# Nixie_Tubes.net
KiCad netlist of a schematic drawn in Altium Designer
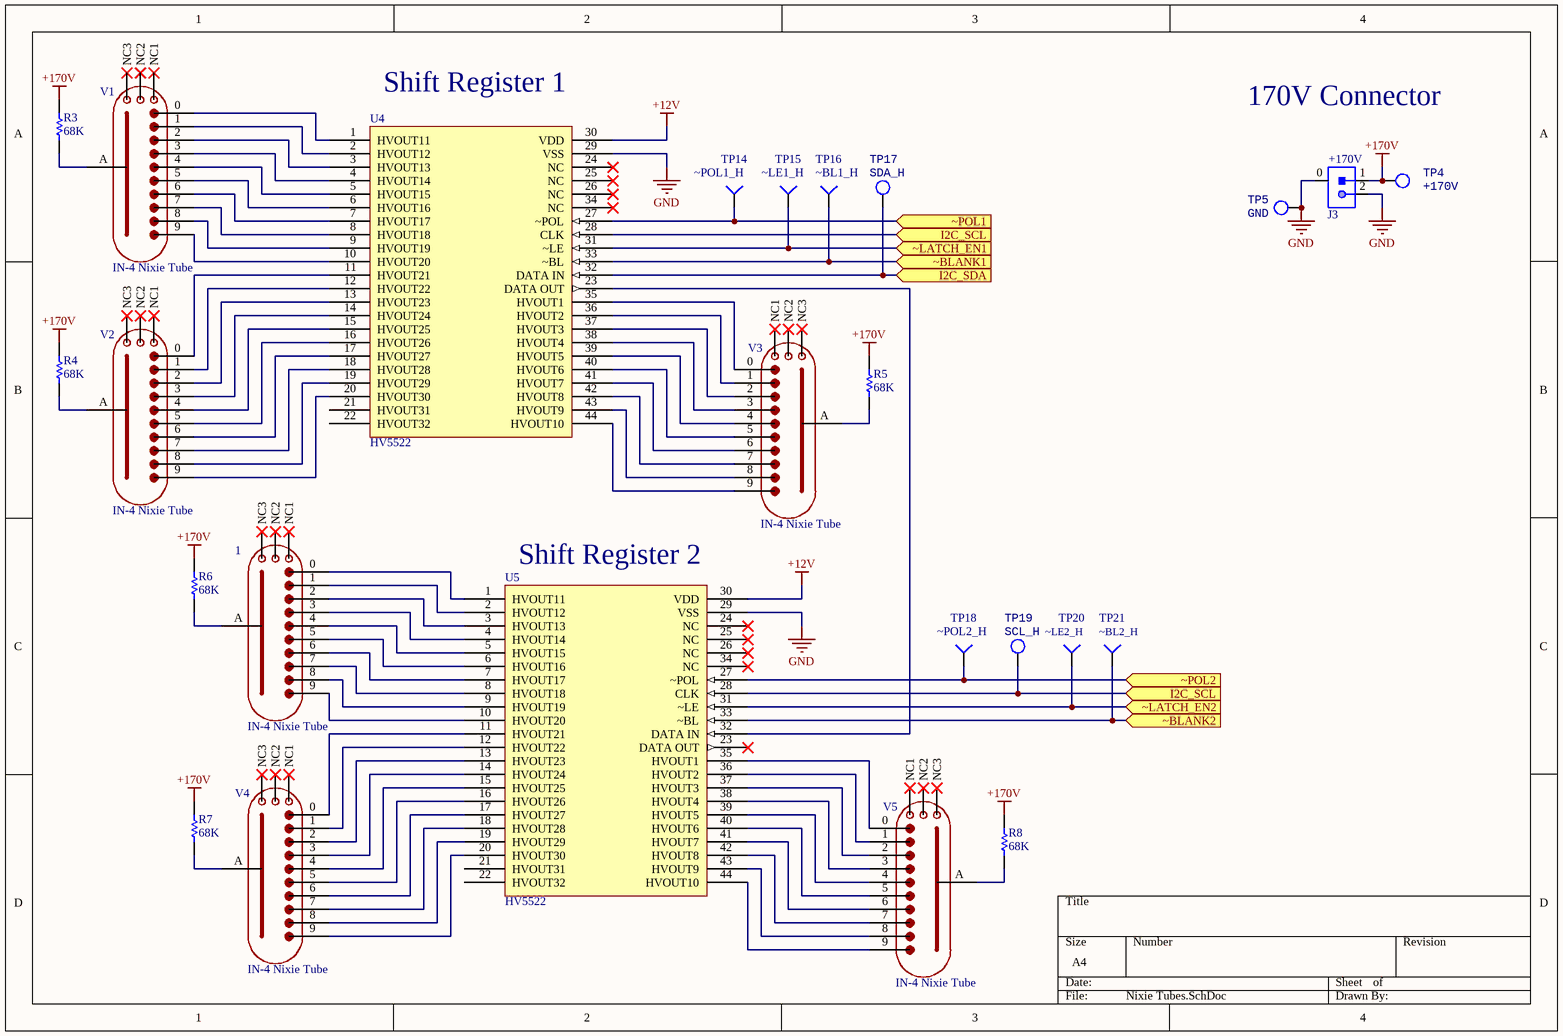
[diagram p0: Nixie Tubes.SchDoc]

(export (version "E")
  (design (tool "Eeschema 10.0.6"))
  (components
    (comp (ref "1") (value "IN-4 Nixie Tube") (libsource (lib "") (part "IN-4 Nixie Tube_1")))
    (comp (ref "J3")
      (value "+170V")
      (footprint "MOLEX-5024940270")
      (description "CONN HEADER SMD RIGHT ANGLE 2MM PITCH")
      (libsource (lib "Schlib_Nixie") (part "CON_2M_SM_RA"))
    )
    (comp (ref "R3")
      (value "68K")
      (footprint "RESC3225X60N")
      (description "RES SMD 68K OHM 1% 0.75W 1210")
      (fields (field (name "TOLERANCE") "1%") (field (name "Comment") "RES_68K_1210"))
      (libsource (lib "Schlib_Nixie") (part "RES_68K_1210"))
    )
    (comp (ref "R4")
      (value "68K")
      (footprint "RESC3225X60N")
      (description "RES SMD 68K OHM 1% 0.75W 1210")
      (fields (field (name "TOLERANCE") "1%") (field (name "Comment") "RES_68K_1210"))
      (libsource (lib "Schlib_Nixie") (part "RES_68K_1210"))
    )
    (comp (ref "R5")
      (value "68K")
      (footprint "RESC3225X60N")
      (description "RES SMD 68K OHM 1% 0.75W 1210")
      (fields (field (name "TOLERANCE") "1%") (field (name "Comment") "RES_68K_1210"))
      (libsource (lib "Schlib_Nixie") (part "RES_68K_1210"))
    )
    (comp (ref "R6")
      (value "68K")
      (footprint "RESC3225X60N")
      (description "RES SMD 68K OHM 1% 0.75W 1210")
      (fields (field (name "TOLERANCE") "1%") (field (name "Comment") "RES_68K_1210"))
      (libsource (lib "Schlib_Nixie") (part "RES_68K_1210"))
    )
    (comp (ref "R7")
      (value "68K")
      (footprint "RESC3225X60N")
      (description "RES SMD 68K OHM 1% 0.75W 1210")
      (fields (field (name "TOLERANCE") "1%") (field (name "Comment") "RES_68K_1210"))
      (libsource (lib "Schlib_Nixie") (part "RES_68K_1210"))
    )
    (comp (ref "R8")
      (value "68K")
      (footprint "RESC3225X60N")
      (description "RES SMD 68K OHM 1% 0.75W 1210")
      (fields (field (name "TOLERANCE") "1%") (field (name "Comment") "RES_68K_1210"))
      (libsource (lib "Schlib_Nixie") (part "RES_68K_1210"))
    )
    (comp (ref "TP4")
      (value "+170V")
      (footprint "TESTPOINT_LOOP")
      (description "Loop testpoint through-hole pad")
      (libsource (lib "Schlib_Nixie") (part "TESTPOINT_LOOP"))
    )
    (comp (ref "TP5")
      (value "GND")
      (footprint "TESTPOINT_LOOP")
      (description "Loop testpoint through-hole pad")
      (libsource (lib "Schlib_Nixie") (part "TESTPOINT_LOOP"))
    )
    (comp (ref "TP14")
      (value "~POL1_H")
      (footprint "TESTPOINT")
      (description "TESTPOINT_SMD")
      (libsource (lib "Schlib_Nixie") (part "TESTPOINT_SMD"))
    )
    (comp (ref "TP15")
      (value "~LE1_H")
      (footprint "TESTPOINT")
      (description "TESTPOINT_SMD")
      (libsource (lib "Schlib_Nixie") (part "TESTPOINT_SMD"))
    )
    (comp (ref "TP16")
      (value "~BL1_H")
      (footprint "TESTPOINT")
      (description "TESTPOINT_SMD")
      (libsource (lib "Schlib_Nixie") (part "TESTPOINT_SMD"))
    )
    (comp (ref "TP17")
      (value "SDA_H")
      (footprint "TESTPOINT_LOOP")
      (description "Loop testpoint through-hole pad")
      (libsource (lib "Schlib_Nixie") (part "TESTPOINT_LOOP"))
    )
    (comp (ref "TP18")
      (value "~POL2_H")
      (footprint "TESTPOINT")
      (description "TESTPOINT_SMD")
      (libsource (lib "Schlib_Nixie") (part "TESTPOINT_SMD"))
    )
    (comp (ref "TP19")
      (value "SCL_H")
      (footprint "TESTPOINT_LOOP")
      (description "Loop testpoint through-hole pad")
      (libsource (lib "Schlib_Nixie") (part "TESTPOINT_LOOP"))
    )
    (comp (ref "TP20")
      (value "~LE2_H")
      (footprint "TESTPOINT")
      (description "TESTPOINT_SMD")
      (libsource (lib "Schlib_Nixie") (part "TESTPOINT_SMD"))
    )
    (comp (ref "TP21")
      (value "~BL2_H")
      (footprint "TESTPOINT")
      (description "TESTPOINT_SMD")
      (libsource (lib "Schlib_Nixie") (part "TESTPOINT_SMD"))
    )
    (comp (ref "U4")
      (value "HV5522")
      (footprint "*QFP80P1320X1320X270-44N")
      (description "IC 32BIT SRL CMOS 220V 44QFP; Shift Shift Register 1 Element 32 Bit 44-PQFP (10x10)")
      (libsource (lib "Schlib_Nixie") (part "HV5522"))
    )
    (comp (ref "U5")
      (value "HV5522")
      (footprint "*QFP80P1320X1320X270-44N")
      (description "IC 32BIT SRL CMOS 220V 44QFP; Shift Shift Register 1 Element 32 Bit 44-PQFP (10x10)")
      (libsource (lib "Schlib_Nixie") (part "HV5522"))
    )
    (comp (ref "V1")
      (value "IN-4 Nixie Tube")
      (footprint "IN-4")
      (libsource (lib "") (part "IN-4 Nixie Tube_1"))
    )
    (comp (ref "V2") (value "IN-4 Nixie Tube") (libsource (lib "") (part "IN-4 Nixie Tube_1")))
    (comp (ref "V3") (value "IN-4 Nixie Tube") (libsource (lib "Schlib_Nixie") (part "IN-4 Nixie Tube")))
    (comp (ref "V4") (value "IN-4 Nixie Tube") (libsource (lib "") (part "IN-4 Nixie Tube_1")))
    (comp (ref "V5") (value "IN-4 Nixie Tube") (libsource (lib "Schlib_Nixie") (part "IN-4 Nixie Tube")))
  )
  (nets
    (net (code "1") (name "+12V") (class "Default")
      (node (ref "U4") (pin "30") (pinfunction "VDD_30") (pintype "power_in"))
      (node (ref "U5") (pin "30") (pinfunction "VDD_30") (pintype "power_in"))
    )
    (net (code "2") (name "+170V") (class "Default")
      (node (ref "J3") (pin "1") (pinfunction "1_1") (pintype "passive"))
      (node (ref "R3") (pin "2") (pinfunction "2_2") (pintype "passive"))
      (node (ref "R4") (pin "2") (pinfunction "2_2") (pintype "passive"))
      (node (ref "R5") (pin "2") (pinfunction "2_2") (pintype "passive"))
      (node (ref "R6") (pin "2") (pinfunction "2_2") (pintype "passive"))
      (node (ref "R7") (pin "2") (pinfunction "2_2") (pintype "passive"))
      (node (ref "R8") (pin "2") (pinfunction "2_2") (pintype "passive"))
      (node (ref "TP4") (pin "1") (pintype "passive"))
    )
    (net (code "3") (name "/I2C_SCL") (class "Default")
      (node (ref "TP19") (pin "1") (pintype "passive"))
      (node (ref "U4") (pin "28") (pinfunction "CLK_28") (pintype "input"))
      (node (ref "U5") (pin "28") (pinfunction "CLK_28") (pintype "input"))
    )
    (net (code "4") (name "/I2C_SDA") (class "Default")
      (node (ref "TP17") (pin "1") (pintype "passive"))
      (node (ref "U4") (pin "32") (pinfunction "DATA_IN_32") (pintype "input"))
    )
    (net (code "5") (name "/~BLANK1") (class "Default")
      (node (ref "TP16") (pin "1") (pinfunction "=value_1") (pintype "passive"))
      (node (ref "U4") (pin "33") (pinfunction "~BL_33") (pintype "input"))
    )
    (net (code "6") (name "/~BLANK2") (class "Default")
      (node (ref "TP21") (pin "1") (pinfunction "=value_1") (pintype "passive"))
      (node (ref "U5") (pin "33") (pinfunction "~BL_33") (pintype "input"))
    )
    (net (code "7") (name "/~LATCH_EN1") (class "Default")
      (node (ref "TP15") (pin "1") (pinfunction "=value_1") (pintype "passive"))
      (node (ref "U4") (pin "31") (pinfunction "~LE_31") (pintype "input"))
    )
    (net (code "8") (name "/~LATCH_EN2") (class "Default")
      (node (ref "TP20") (pin "1") (pinfunction "=value_1") (pintype "passive"))
      (node (ref "U5") (pin "31") (pinfunction "~LE_31") (pintype "input"))
    )
    (net (code "9") (name "/~POL1") (class "Default")
      (node (ref "TP14") (pin "1") (pinfunction "=value_1") (pintype "passive"))
      (node (ref "U4") (pin "27") (pinfunction "~POL_27") (pintype "input"))
    )
    (net (code "10") (name "/~POL2") (class "Default")
      (node (ref "TP18") (pin "1") (pinfunction "=value_1") (pintype "passive"))
      (node (ref "U5") (pin "27") (pinfunction "~POL_27") (pintype "input"))
    )
    (net (code "11") (name "GND") (class "Default")
      (node (ref "J3") (pin "0") (pinfunction "0_0") (pintype "passive"))
      (node (ref "J3") (pin "2") (pinfunction "2_2") (pintype "passive"))
      (node (ref "TP5") (pin "1") (pintype "passive"))
      (node (ref "U4") (pin "29") (pinfunction "VSS_29") (pintype "passive"))
      (node (ref "U5") (pin "29") (pinfunction "VSS_29") (pintype "passive"))
    )
    (net (code "12") (name "Net-(U4-DATA_OUT)") (class "Default")
      (node (ref "U4") (pin "23") (pinfunction "DATA_OUT_23") (pintype "output"))
      (node (ref "U5") (pin "32") (pinfunction "DATA_IN_32") (pintype "input"))
    )
    (net (code "13") (name "unconnected-(1-NC1-Pad10)") (class "Default")
      (node (ref "1") (pin "10") (pinfunction "NC1_10") (pintype "passive"))
    )
    (net (code "14") (name "unconnected-(1-NC2-Pad11)") (class "Default")
      (node (ref "1") (pin "11") (pinfunction "NC2_11") (pintype "passive"))
    )
    (net (code "15") (name "unconnected-(1-NC3-Pad12)") (class "Default")
      (node (ref "1") (pin "12") (pinfunction "NC3_12") (pintype "passive"))
    )
    (net (code "16") (name "unconnected-(1-P8-Pad0)") (class "Default")
      (node (ref "1") (pin "0") (pinfunction "P8_0") (pintype "passive"))
    )
    (net (code "17") (name "unconnected-(1-Pad1)") (class "Default")
      (node (ref "1") (pin "1") (pintype "passive"))
    )
    (net (code "18") (name "unconnected-(1-Pad2)") (class "Default")
      (node (ref "1") (pin "2") (pintype "passive"))
    )
    (net (code "19") (name "unconnected-(1-Pad3)") (class "Default")
      (node (ref "1") (pin "3") (pintype "passive"))
    )
    (net (code "20") (name "unconnected-(1-Pad4)") (class "Default")
      (node (ref "1") (pin "4") (pintype "passive"))
    )
    (net (code "21") (name "unconnected-(1-Pad5)") (class "Default")
      (node (ref "1") (pin "5") (pintype "passive"))
    )
    (net (code "22") (name "unconnected-(1-Pad6)") (class "Default")
      (node (ref "1") (pin "6") (pintype "passive"))
    )
    (net (code "23") (name "unconnected-(1-Pad7)") (class "Default")
      (node (ref "1") (pin "7") (pintype "passive"))
    )
    (net (code "24") (name "unconnected-(1-Pad8)") (class "Default")
      (node (ref "1") (pin "8") (pintype "passive"))
    )
    (net (code "25") (name "unconnected-(1-Pad9)") (class "Default")
      (node (ref "1") (pin "9") (pintype "passive"))
    )
    (net (code "26") (name "unconnected-(1-PadA)") (class "Default")
      (node (ref "1") (pin "A") (pintype "passive"))
    )
    (net (code "27") (name "unconnected-(R3-Pad1)") (class "Default")
      (node (ref "R3") (pin "1") (pinfunction "1_1") (pintype "passive"))
    )
    (net (code "28") (name "unconnected-(R4-Pad1)") (class "Default")
      (node (ref "R4") (pin "1") (pinfunction "1_1") (pintype "passive"))
    )
    (net (code "29") (name "unconnected-(R5-Pad1)") (class "Default")
      (node (ref "R5") (pin "1") (pinfunction "1_1") (pintype "passive"))
    )
    (net (code "30") (name "unconnected-(R6-Pad1)") (class "Default")
      (node (ref "R6") (pin "1") (pinfunction "1_1") (pintype "passive"))
    )
    (net (code "31") (name "unconnected-(R7-Pad1)") (class "Default")
      (node (ref "R7") (pin "1") (pinfunction "1_1") (pintype "passive"))
    )
    (net (code "32") (name "unconnected-(R8-Pad1)") (class "Default")
      (node (ref "R8") (pin "1") (pinfunction "1_1") (pintype "passive"))
    )
    (net (code "33") (name "unconnected-(U4-HVOUT1-Pad35)") (class "Default")
      (node (ref "U4") (pin "35") (pinfunction "HVOUT1_35") (pintype "passive"))
    )
    (net (code "34") (name "unconnected-(U4-HVOUT2-Pad36)") (class "Default")
      (node (ref "U4") (pin "36") (pinfunction "HVOUT2_36") (pintype "passive"))
    )
    (net (code "35") (name "unconnected-(U4-HVOUT3-Pad37)") (class "Default")
      (node (ref "U4") (pin "37") (pinfunction "HVOUT3_37") (pintype "passive"))
    )
    (net (code "36") (name "unconnected-(U4-HVOUT4-Pad38)") (class "Default")
      (node (ref "U4") (pin "38") (pinfunction "HVOUT4_38") (pintype "passive"))
    )
    (net (code "37") (name "unconnected-(U4-HVOUT5-Pad39)") (class "Default")
      (node (ref "U4") (pin "39") (pinfunction "HVOUT5_39") (pintype "passive"))
    )
    (net (code "38") (name "unconnected-(U4-HVOUT6-Pad40)") (class "Default")
      (node (ref "U4") (pin "40") (pinfunction "HVOUT6_40") (pintype "passive"))
    )
    (net (code "39") (name "unconnected-(U4-HVOUT7-Pad41)") (class "Default")
      (node (ref "U4") (pin "41") (pinfunction "HVOUT7_41") (pintype "passive"))
    )
    (net (code "40") (name "unconnected-(U4-HVOUT8-Pad42)") (class "Default")
      (node (ref "U4") (pin "42") (pinfunction "HVOUT8_42") (pintype "passive"))
    )
    (net (code "41") (name "unconnected-(U4-HVOUT9-Pad43)") (class "Default")
      (node (ref "U4") (pin "43") (pinfunction "HVOUT9_43") (pintype "passive"))
    )
    (net (code "42") (name "unconnected-(U4-HVOUT10-Pad44)") (class "Default")
      (node (ref "U4") (pin "44") (pinfunction "HVOUT10_44") (pintype "passive"))
    )
    (net (code "43") (name "unconnected-(U4-HVOUT11-Pad1)") (class "Default")
      (node (ref "U4") (pin "1") (pinfunction "HVOUT11_1") (pintype "open_collector"))
    )
    (net (code "44") (name "unconnected-(U4-HVOUT12-Pad2)") (class "Default")
      (node (ref "U4") (pin "2") (pinfunction "HVOUT12_2") (pintype "passive"))
    )
    (net (code "45") (name "unconnected-(U4-HVOUT13-Pad3)") (class "Default")
      (node (ref "U4") (pin "3") (pinfunction "HVOUT13_3") (pintype "passive"))
    )
    (net (code "46") (name "unconnected-(U4-HVOUT14-Pad4)") (class "Default")
      (node (ref "U4") (pin "4") (pinfunction "HVOUT14_4") (pintype "passive"))
    )
    (net (code "47") (name "unconnected-(U4-HVOUT15-Pad5)") (class "Default")
      (node (ref "U4") (pin "5") (pinfunction "HVOUT15_5") (pintype "passive"))
    )
    (net (code "48") (name "unconnected-(U4-HVOUT16-Pad6)") (class "Default")
      (node (ref "U4") (pin "6") (pinfunction "HVOUT16_6") (pintype "passive"))
    )
    (net (code "49") (name "unconnected-(U4-HVOUT17-Pad7)") (class "Default")
      (node (ref "U4") (pin "7") (pinfunction "HVOUT17_7") (pintype "passive"))
    )
    (net (code "50") (name "unconnected-(U4-HVOUT18-Pad8)") (class "Default")
      (node (ref "U4") (pin "8") (pinfunction "HVOUT18_8") (pintype "passive"))
    )
    (net (code "51") (name "unconnected-(U4-HVOUT19-Pad9)") (class "Default")
      (node (ref "U4") (pin "9") (pinfunction "HVOUT19_9") (pintype "passive"))
    )
    (net (code "52") (name "unconnected-(U4-HVOUT20-Pad10)") (class "Default")
      (node (ref "U4") (pin "10") (pinfunction "HVOUT20_10") (pintype "passive"))
    )
    (net (code "53") (name "unconnected-(U4-HVOUT21-Pad11)") (class "Default")
      (node (ref "U4") (pin "11") (pinfunction "HVOUT21_11") (pintype "passive"))
    )
    (net (code "54") (name "unconnected-(U4-HVOUT22-Pad12)") (class "Default")
      (node (ref "U4") (pin "12") (pinfunction "HVOUT22_12") (pintype "passive"))
    )
    (net (code "55") (name "unconnected-(U4-HVOUT23-Pad13)") (class "Default")
      (node (ref "U4") (pin "13") (pinfunction "HVOUT23_13") (pintype "passive"))
    )
    (net (code "56") (name "unconnected-(U4-HVOUT24-Pad14)") (class "Default")
      (node (ref "U4") (pin "14") (pinfunction "HVOUT24_14") (pintype "passive"))
    )
    (net (code "57") (name "unconnected-(U4-HVOUT25-Pad15)") (class "Default")
      (node (ref "U4") (pin "15") (pinfunction "HVOUT25_15") (pintype "passive"))
    )
    (net (code "58") (name "unconnected-(U4-HVOUT26-Pad16)") (class "Default")
      (node (ref "U4") (pin "16") (pinfunction "HVOUT26_16") (pintype "passive"))
    )
    (net (code "59") (name "unconnected-(U4-HVOUT27-Pad17)") (class "Default")
      (node (ref "U4") (pin "17") (pinfunction "HVOUT27_17") (pintype "passive"))
    )
    (net (code "60") (name "unconnected-(U4-HVOUT28-Pad18)") (class "Default")
      (node (ref "U4") (pin "18") (pinfunction "HVOUT28_18") (pintype "passive"))
    )
    (net (code "61") (name "unconnected-(U4-HVOUT29-Pad19)") (class "Default")
      (node (ref "U4") (pin "19") (pinfunction "HVOUT29_19") (pintype "passive"))
    )
    (net (code "62") (name "unconnected-(U4-HVOUT30-Pad20)") (class "Default")
      (node (ref "U4") (pin "20") (pinfunction "HVOUT30_20") (pintype "passive"))
    )
    (net (code "63") (name "unconnected-(U4-HVOUT31-Pad21)") (class "Default")
      (node (ref "U4") (pin "21") (pinfunction "HVOUT31_21") (pintype "passive"))
    )
    (net (code "64") (name "unconnected-(U4-HVOUT32-Pad22)") (class "Default")
      (node (ref "U4") (pin "22") (pinfunction "HVOUT32_22") (pintype "passive"))
    )
    (net (code "65") (name "unconnected-(U4-NC-Pad24)") (class "Default")
      (node (ref "U4") (pin "24") (pinfunction "NC_24") (pintype "passive+no_connect"))
    )
    (net (code "66") (name "unconnected-(U4-NC-Pad25)") (class "Default")
      (node (ref "U4") (pin "25") (pinfunction "NC_25") (pintype "passive+no_connect"))
    )
    (net (code "67") (name "unconnected-(U4-NC-Pad26)") (class "Default")
      (node (ref "U4") (pin "26") (pinfunction "NC_26") (pintype "passive+no_connect"))
    )
    (net (code "68") (name "unconnected-(U4-NC-Pad34)") (class "Default")
      (node (ref "U4") (pin "34") (pinfunction "NC_34") (pintype "passive+no_connect"))
    )
    (net (code "69") (name "unconnected-(U5-DATA_OUT-Pad23)") (class "Default")
      (node (ref "U5") (pin "23") (pinfunction "DATA_OUT_23") (pintype "output+no_connect"))
    )
    (net (code "70") (name "unconnected-(U5-HVOUT1-Pad35)") (class "Default")
      (node (ref "U5") (pin "35") (pinfunction "HVOUT1_35") (pintype "passive"))
    )
    (net (code "71") (name "unconnected-(U5-HVOUT2-Pad36)") (class "Default")
      (node (ref "U5") (pin "36") (pinfunction "HVOUT2_36") (pintype "passive"))
    )
    (net (code "72") (name "unconnected-(U5-HVOUT3-Pad37)") (class "Default")
      (node (ref "U5") (pin "37") (pinfunction "HVOUT3_37") (pintype "passive"))
    )
    (net (code "73") (name "unconnected-(U5-HVOUT4-Pad38)") (class "Default")
      (node (ref "U5") (pin "38") (pinfunction "HVOUT4_38") (pintype "passive"))
    )
    (net (code "74") (name "unconnected-(U5-HVOUT5-Pad39)") (class "Default")
      (node (ref "U5") (pin "39") (pinfunction "HVOUT5_39") (pintype "passive"))
    )
    (net (code "75") (name "unconnected-(U5-HVOUT6-Pad40)") (class "Default")
      (node (ref "U5") (pin "40") (pinfunction "HVOUT6_40") (pintype "passive"))
    )
    (net (code "76") (name "unconnected-(U5-HVOUT7-Pad41)") (class "Default")
      (node (ref "U5") (pin "41") (pinfunction "HVOUT7_41") (pintype "passive"))
    )
    (net (code "77") (name "unconnected-(U5-HVOUT8-Pad42)") (class "Default")
      (node (ref "U5") (pin "42") (pinfunction "HVOUT8_42") (pintype "passive"))
    )
    (net (code "78") (name "unconnected-(U5-HVOUT9-Pad43)") (class "Default")
      (node (ref "U5") (pin "43") (pinfunction "HVOUT9_43") (pintype "passive"))
    )
    (net (code "79") (name "unconnected-(U5-HVOUT10-Pad44)") (class "Default")
      (node (ref "U5") (pin "44") (pinfunction "HVOUT10_44") (pintype "passive"))
    )
    (net (code "80") (name "unconnected-(U5-HVOUT11-Pad1)") (class "Default")
      (node (ref "U5") (pin "1") (pinfunction "HVOUT11_1") (pintype "open_collector"))
    )
    (net (code "81") (name "unconnected-(U5-HVOUT12-Pad2)") (class "Default")
      (node (ref "U5") (pin "2") (pinfunction "HVOUT12_2") (pintype "passive"))
    )
    (net (code "82") (name "unconnected-(U5-HVOUT13-Pad3)") (class "Default")
      (node (ref "U5") (pin "3") (pinfunction "HVOUT13_3") (pintype "passive"))
    )
    (net (code "83") (name "unconnected-(U5-HVOUT14-Pad4)") (class "Default")
      (node (ref "U5") (pin "4") (pinfunction "HVOUT14_4") (pintype "passive"))
    )
    (net (code "84") (name "unconnected-(U5-HVOUT15-Pad5)") (class "Default")
      (node (ref "U5") (pin "5") (pinfunction "HVOUT15_5") (pintype "passive"))
    )
    (net (code "85") (name "unconnected-(U5-HVOUT16-Pad6)") (class "Default")
      (node (ref "U5") (pin "6") (pinfunction "HVOUT16_6") (pintype "passive"))
    )
    (net (code "86") (name "unconnected-(U5-HVOUT17-Pad7)") (class "Default")
      (node (ref "U5") (pin "7") (pinfunction "HVOUT17_7") (pintype "passive"))
    )
    (net (code "87") (name "unconnected-(U5-HVOUT18-Pad8)") (class "Default")
      (node (ref "U5") (pin "8") (pinfunction "HVOUT18_8") (pintype "passive"))
    )
    (net (code "88") (name "unconnected-(U5-HVOUT19-Pad9)") (class "Default")
      (node (ref "U5") (pin "9") (pinfunction "HVOUT19_9") (pintype "passive"))
    )
    (net (code "89") (name "unconnected-(U5-HVOUT20-Pad10)") (class "Default")
      (node (ref "U5") (pin "10") (pinfunction "HVOUT20_10") (pintype "passive"))
    )
    (net (code "90") (name "unconnected-(U5-HVOUT21-Pad11)") (class "Default")
      (node (ref "U5") (pin "11") (pinfunction "HVOUT21_11") (pintype "passive"))
    )
    (net (code "91") (name "unconnected-(U5-HVOUT22-Pad12)") (class "Default")
      (node (ref "U5") (pin "12") (pinfunction "HVOUT22_12") (pintype "passive"))
    )
    (net (code "92") (name "unconnected-(U5-HVOUT23-Pad13)") (class "Default")
      (node (ref "U5") (pin "13") (pinfunction "HVOUT23_13") (pintype "passive"))
    )
    (net (code "93") (name "unconnected-(U5-HVOUT24-Pad14)") (class "Default")
      (node (ref "U5") (pin "14") (pinfunction "HVOUT24_14") (pintype "passive"))
    )
    (net (code "94") (name "unconnected-(U5-HVOUT25-Pad15)") (class "Default")
      (node (ref "U5") (pin "15") (pinfunction "HVOUT25_15") (pintype "passive"))
    )
    (net (code "95") (name "unconnected-(U5-HVOUT26-Pad16)") (class "Default")
      (node (ref "U5") (pin "16") (pinfunction "HVOUT26_16") (pintype "passive"))
    )
    (net (code "96") (name "unconnected-(U5-HVOUT27-Pad17)") (class "Default")
      (node (ref "U5") (pin "17") (pinfunction "HVOUT27_17") (pintype "passive"))
    )
    (net (code "97") (name "unconnected-(U5-HVOUT28-Pad18)") (class "Default")
      (node (ref "U5") (pin "18") (pinfunction "HVOUT28_18") (pintype "passive"))
    )
    (net (code "98") (name "unconnected-(U5-HVOUT29-Pad19)") (class "Default")
      (node (ref "U5") (pin "19") (pinfunction "HVOUT29_19") (pintype "passive"))
    )
    (net (code "99") (name "unconnected-(U5-HVOUT30-Pad20)") (class "Default")
      (node (ref "U5") (pin "20") (pinfunction "HVOUT30_20") (pintype "passive"))
    )
    (net (code "100") (name "unconnected-(U5-HVOUT31-Pad21)") (class "Default")
      (node (ref "U5") (pin "21") (pinfunction "HVOUT31_21") (pintype "passive"))
    )
    (net (code "101") (name "unconnected-(U5-HVOUT32-Pad22)") (class "Default")
      (node (ref "U5") (pin "22") (pinfunction "HVOUT32_22") (pintype "passive"))
    )
    (net (code "102") (name "unconnected-(U5-NC-Pad24)") (class "Default")
      (node (ref "U5") (pin "24") (pinfunction "NC_24") (pintype "passive+no_connect"))
    )
    (net (code "103") (name "unconnected-(U5-NC-Pad25)") (class "Default")
      (node (ref "U5") (pin "25") (pinfunction "NC_25") (pintype "passive+no_connect"))
    )
    (net (code "104") (name "unconnected-(U5-NC-Pad26)") (class "Default")
      (node (ref "U5") (pin "26") (pinfunction "NC_26") (pintype "passive+no_connect"))
    )
    (net (code "105") (name "unconnected-(U5-NC-Pad34)") (class "Default")
      (node (ref "U5") (pin "34") (pinfunction "NC_34") (pintype "passive+no_connect"))
    )
    (net (code "106") (name "unconnected-(V1-NC1-Pad10)") (class "Default")
      (node (ref "V1") (pin "10") (pinfunction "NC1_10") (pintype "passive"))
    )
    (net (code "107") (name "unconnected-(V1-NC2-Pad11)") (class "Default")
      (node (ref "V1") (pin "11") (pinfunction "NC2_11") (pintype "passive"))
    )
    (net (code "108") (name "unconnected-(V1-NC3-Pad12)") (class "Default")
      (node (ref "V1") (pin "12") (pinfunction "NC3_12") (pintype "passive"))
    )
    (net (code "109") (name "unconnected-(V1-P8-Pad0)") (class "Default")
      (node (ref "V1") (pin "0") (pinfunction "P8_0") (pintype "passive"))
    )
    (net (code "110") (name "unconnected-(V1-Pad1)") (class "Default")
      (node (ref "V1") (pin "1") (pintype "passive"))
    )
    (net (code "111") (name "unconnected-(V1-Pad2)") (class "Default")
      (node (ref "V1") (pin "2") (pintype "passive"))
    )
    (net (code "112") (name "unconnected-(V1-Pad3)") (class "Default")
      (node (ref "V1") (pin "3") (pintype "passive"))
    )
    (net (code "113") (name "unconnected-(V1-Pad4)") (class "Default")
      (node (ref "V1") (pin "4") (pintype "passive"))
    )
    (net (code "114") (name "unconnected-(V1-Pad5)") (class "Default")
      (node (ref "V1") (pin "5") (pintype "passive"))
    )
    (net (code "115") (name "unconnected-(V1-Pad6)") (class "Default")
      (node (ref "V1") (pin "6") (pintype "passive"))
    )
    (net (code "116") (name "unconnected-(V1-Pad7)") (class "Default")
      (node (ref "V1") (pin "7") (pintype "passive"))
    )
    (net (code "117") (name "unconnected-(V1-Pad8)") (class "Default")
      (node (ref "V1") (pin "8") (pintype "passive"))
    )
    (net (code "118") (name "unconnected-(V1-Pad9)") (class "Default")
      (node (ref "V1") (pin "9") (pintype "passive"))
    )
    (net (code "119") (name "unconnected-(V1-PadA)") (class "Default")
      (node (ref "V1") (pin "A") (pintype "passive"))
    )
    (net (code "120") (name "unconnected-(V2-NC1-Pad10)") (class "Default")
      (node (ref "V2") (pin "10") (pinfunction "NC1_10") (pintype "passive"))
    )
    (net (code "121") (name "unconnected-(V2-NC2-Pad11)") (class "Default")
      (node (ref "V2") (pin "11") (pinfunction "NC2_11") (pintype "passive"))
    )
    (net (code "122") (name "unconnected-(V2-NC3-Pad12)") (class "Default")
      (node (ref "V2") (pin "12") (pinfunction "NC3_12") (pintype "passive"))
    )
    (net (code "123") (name "unconnected-(V2-P8-Pad0)") (class "Default")
      (node (ref "V2") (pin "0") (pinfunction "P8_0") (pintype "passive"))
    )
    (net (code "124") (name "unconnected-(V2-Pad1)") (class "Default")
      (node (ref "V2") (pin "1") (pintype "passive"))
    )
    (net (code "125") (name "unconnected-(V2-Pad2)") (class "Default")
      (node (ref "V2") (pin "2") (pintype "passive"))
    )
    (net (code "126") (name "unconnected-(V2-Pad3)") (class "Default")
      (node (ref "V2") (pin "3") (pintype "passive"))
    )
    (net (code "127") (name "unconnected-(V2-Pad4)") (class "Default")
      (node (ref "V2") (pin "4") (pintype "passive"))
    )
    (net (code "128") (name "unconnected-(V2-Pad5)") (class "Default")
      (node (ref "V2") (pin "5") (pintype "passive"))
    )
    (net (code "129") (name "unconnected-(V2-Pad6)") (class "Default")
      (node (ref "V2") (pin "6") (pintype "passive"))
    )
    (net (code "130") (name "unconnected-(V2-Pad7)") (class "Default")
      (node (ref "V2") (pin "7") (pintype "passive"))
    )
    (net (code "131") (name "unconnected-(V2-Pad8)") (class "Default")
      (node (ref "V2") (pin "8") (pintype "passive"))
    )
    (net (code "132") (name "unconnected-(V2-Pad9)") (class "Default")
      (node (ref "V2") (pin "9") (pintype "passive"))
    )
    (net (code "133") (name "unconnected-(V2-PadA)") (class "Default")
      (node (ref "V2") (pin "A") (pintype "passive"))
    )
    (net (code "134") (name "unconnected-(V3-NC1-Pad10)") (class "Default")
      (node (ref "V3") (pin "10") (pinfunction "NC1_10") (pintype "passive"))
    )
    (net (code "135") (name "unconnected-(V3-NC2-Pad11)") (class "Default")
      (node (ref "V3") (pin "11") (pinfunction "NC2_11") (pintype "passive"))
    )
    (net (code "136") (name "unconnected-(V3-NC3-Pad12)") (class "Default")
      (node (ref "V3") (pin "12") (pinfunction "NC3_12") (pintype "passive"))
    )
    (net (code "137") (name "unconnected-(V3-P8-Pad0)") (class "Default")
      (node (ref "V3") (pin "0") (pinfunction "P8_0") (pintype "passive"))
    )
    (net (code "138") (name "unconnected-(V3-Pad1)") (class "Default")
      (node (ref "V3") (pin "1") (pintype "passive"))
    )
    (net (code "139") (name "unconnected-(V3-Pad2)") (class "Default")
      (node (ref "V3") (pin "2") (pintype "passive"))
    )
    (net (code "140") (name "unconnected-(V3-Pad3)") (class "Default")
      (node (ref "V3") (pin "3") (pintype "passive"))
    )
    (net (code "141") (name "unconnected-(V3-Pad4)") (class "Default")
      (node (ref "V3") (pin "4") (pintype "passive"))
    )
    (net (code "142") (name "unconnected-(V3-Pad5)") (class "Default")
      (node (ref "V3") (pin "5") (pintype "passive"))
    )
    (net (code "143") (name "unconnected-(V3-Pad6)") (class "Default")
      (node (ref "V3") (pin "6") (pintype "passive"))
    )
    (net (code "144") (name "unconnected-(V3-Pad7)") (class "Default")
      (node (ref "V3") (pin "7") (pintype "passive"))
    )
    (net (code "145") (name "unconnected-(V3-Pad8)") (class "Default")
      (node (ref "V3") (pin "8") (pintype "passive"))
    )
    (net (code "146") (name "unconnected-(V3-Pad9)") (class "Default")
      (node (ref "V3") (pin "9") (pintype "passive"))
    )
    (net (code "147") (name "unconnected-(V3-PadA)") (class "Default")
      (node (ref "V3") (pin "A") (pintype "passive"))
    )
    (net (code "148") (name "unconnected-(V4-NC1-Pad10)") (class "Default")
      (node (ref "V4") (pin "10") (pinfunction "NC1_10") (pintype "passive"))
    )
    (net (code "149") (name "unconnected-(V4-NC2-Pad11)") (class "Default")
      (node (ref "V4") (pin "11") (pinfunction "NC2_11") (pintype "passive"))
    )
    (net (code "150") (name "unconnected-(V4-NC3-Pad12)") (class "Default")
      (node (ref "V4") (pin "12") (pinfunction "NC3_12") (pintype "passive"))
    )
    (net (code "151") (name "unconnected-(V4-P8-Pad0)") (class "Default")
      (node (ref "V4") (pin "0") (pinfunction "P8_0") (pintype "passive"))
    )
    (net (code "152") (name "unconnected-(V4-Pad1)") (class "Default")
      (node (ref "V4") (pin "1") (pintype "passive"))
    )
    (net (code "153") (name "unconnected-(V4-Pad2)") (class "Default")
      (node (ref "V4") (pin "2") (pintype "passive"))
    )
    (net (code "154") (name "unconnected-(V4-Pad3)") (class "Default")
      (node (ref "V4") (pin "3") (pintype "passive"))
    )
    (net (code "155") (name "unconnected-(V4-Pad4)") (class "Default")
      (node (ref "V4") (pin "4") (pintype "passive"))
    )
    (net (code "156") (name "unconnected-(V4-Pad5)") (class "Default")
      (node (ref "V4") (pin "5") (pintype "passive"))
    )
    (net (code "157") (name "unconnected-(V4-Pad6)") (class "Default")
      (node (ref "V4") (pin "6") (pintype "passive"))
    )
    (net (code "158") (name "unconnected-(V4-Pad7)") (class "Default")
      (node (ref "V4") (pin "7") (pintype "passive"))
    )
    (net (code "159") (name "unconnected-(V4-Pad8)") (class "Default")
      (node (ref "V4") (pin "8") (pintype "passive"))
    )
    (net (code "160") (name "unconnected-(V4-Pad9)") (class "Default")
      (node (ref "V4") (pin "9") (pintype "passive"))
    )
    (net (code "161") (name "unconnected-(V4-PadA)") (class "Default")
      (node (ref "V4") (pin "A") (pintype "passive"))
    )
    (net (code "162") (name "unconnected-(V5-NC1-Pad10)") (class "Default")
      (node (ref "V5") (pin "10") (pinfunction "NC1_10") (pintype "passive"))
    )
    (net (code "163") (name "unconnected-(V5-NC2-Pad11)") (class "Default")
      (node (ref "V5") (pin "11") (pinfunction "NC2_11") (pintype "passive"))
    )
    (net (code "164") (name "unconnected-(V5-NC3-Pad12)") (class "Default")
      (node (ref "V5") (pin "12") (pinfunction "NC3_12") (pintype "passive"))
    )
    (net (code "165") (name "unconnected-(V5-P8-Pad0)") (class "Default")
      (node (ref "V5") (pin "0") (pinfunction "P8_0") (pintype "passive"))
    )
    (net (code "166") (name "unconnected-(V5-Pad1)") (class "Default")
      (node (ref "V5") (pin "1") (pintype "passive"))
    )
    (net (code "167") (name "unconnected-(V5-Pad2)") (class "Default")
      (node (ref "V5") (pin "2") (pintype "passive"))
    )
    (net (code "168") (name "unconnected-(V5-Pad3)") (class "Default")
      (node (ref "V5") (pin "3") (pintype "passive"))
    )
    (net (code "169") (name "unconnected-(V5-Pad4)") (class "Default")
      (node (ref "V5") (pin "4") (pintype "passive"))
    )
    (net (code "170") (name "unconnected-(V5-Pad5)") (class "Default")
      (node (ref "V5") (pin "5") (pintype "passive"))
    )
    (net (code "171") (name "unconnected-(V5-Pad6)") (class "Default")
      (node (ref "V5") (pin "6") (pintype "passive"))
    )
    (net (code "172") (name "unconnected-(V5-Pad7)") (class "Default")
      (node (ref "V5") (pin "7") (pintype "passive"))
    )
    (net (code "173") (name "unconnected-(V5-Pad8)") (class "Default")
      (node (ref "V5") (pin "8") (pintype "passive"))
    )
    (net (code "174") (name "unconnected-(V5-Pad9)") (class "Default")
      (node (ref "V5") (pin "9") (pintype "passive"))
    )
    (net (code "175") (name "unconnected-(V5-PadA)") (class "Default")
      (node (ref "V5") (pin "A") (pintype "passive"))
    )
  )
)
